# CC2564MODACMOG_1L.net
KiCad netlist of a schematic drawn in EAGLE
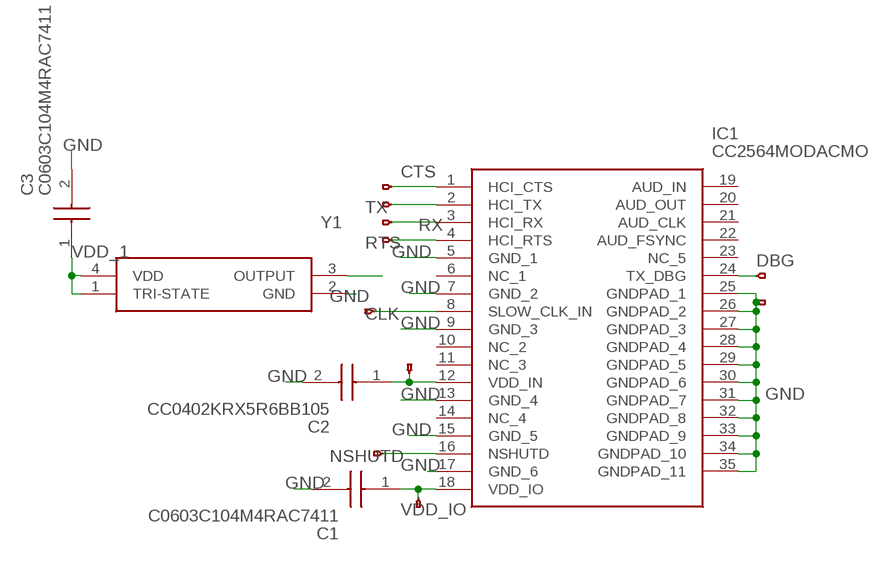
[diagram p0: schematic, sheet 1]

(export (version "E")
  (design (tool "Eeschema 10.0.6"))
  (components
    (comp (ref "C1")
      (value "C0603C104M4RAC7411")
      (footprint "eagle-import:CAPC1608X95N")
      (fields (field (name "MOUSER_PART_NUMBER") "80-C0603C104M4R7411"))
      (libsource (lib "eagle-import") (part "C0603C104M4RAC7411"))
    )
    (comp (ref "C2")
      (value "CC0402KRX5R6BB105")
      (footprint "eagle-import:CAPC1005X55N")
      (fields (field (name "MOUSER_PART_NUMBER") "603-CC402KRX5R6BB105"))
      (libsource (lib "eagle-import") (part "CC0402KRX5R6BB105"))
    )
    (comp (ref "C3")
      (value "C0603C104M4RAC7411")
      (footprint "eagle-import:CAPC1608X95N")
      (fields (field (name "MOUSER_PART_NUMBER") "80-C0603C104M4R7411"))
      (libsource (lib "eagle-import") (part "C0603C104M4RAC7411"))
    )
    (comp (ref "IC1")
      (value "CC2564MODACMOG")
      (footprint "eagle-import:MOG0035A")
      (fields (field (name "MOUSER_PART_NUMBER") "595-CC2564MODACMOG"))
      (libsource (lib "eagle-import") (part "CC2564MODACMOG"))
    )
    (comp (ref "JP1")
      (value "HEADERHOLE-HEADERHOLE")
      (footprint "eagle-import:1X1-HEADER-HOLE")
      (libsource (lib "eagle-import") (part "HEADERHOLE-HEADERHOLE"))
    )
    (comp (ref "JP2")
      (value "HEADERHOLE-HEADERHOLE")
      (footprint "eagle-import:1X1-HEADER-HOLE")
      (libsource (lib "eagle-import") (part "HEADERHOLE-HEADERHOLE"))
    )
    (comp (ref "JP7")
      (value "HEADERHOLE-HEADERHOLE")
      (footprint "eagle-import:1X1-HEADER-HOLE")
      (libsource (lib "eagle-import") (part "HEADERHOLE-HEADERHOLE"))
    )
    (comp (ref "JP8")
      (value "HEADERHOLE-HEADERHOLE")
      (footprint "eagle-import:1X1-HEADER-HOLE")
      (libsource (lib "eagle-import") (part "HEADERHOLE-HEADERHOLE"))
    )
    (comp (ref "JP9")
      (value "HEADERHOLE-HEADERHOLE")
      (footprint "eagle-import:1X1-HEADER-HOLE")
      (libsource (lib "eagle-import") (part "HEADERHOLE-HEADERHOLE"))
    )
    (comp (ref "JP10")
      (value "HEADERHOLE-HEADERHOLE")
      (footprint "eagle-import:1X1-HEADER-HOLE")
      (libsource (lib "eagle-import") (part "HEADERHOLE-HEADERHOLE"))
    )
    (comp (ref "JP11")
      (value "HEADERHOLE-HEADERHOLE")
      (footprint "eagle-import:1X1-HEADER-HOLE")
      (libsource (lib "eagle-import") (part "HEADERHOLE-HEADERHOLE"))
    )
    (comp (ref "JP12")
      (value "HEADERHOLE-HEADERHOLE")
      (footprint "eagle-import:1X1-HEADER-HOLE")
      (libsource (lib "eagle-import") (part "HEADERHOLE-HEADERHOLE"))
    )
    (comp (ref "JP13")
      (value "HEADERHOLE-HEADERHOLE")
      (footprint "eagle-import:1X1-HEADER-HOLE")
      (libsource (lib "eagle-import") (part "HEADERHOLE-HEADERHOLE"))
    )
    (comp (ref "JP14")
      (value "HEADERHOLE-HEADERHOLE")
      (footprint "eagle-import:1X1-HEADER-HOLE")
      (libsource (lib "eagle-import") (part "HEADERHOLE-HEADERHOLE"))
    )
    (comp (ref "Y1")
      (value "ECS-327MVATX-1-CN-TR")
      (footprint "eagle-import:ECS327MVATX1CNTR")
      (fields (field (name "MOUSER_PART_NUMBER") "520-327MVATX-1-CNT"))
      (libsource (lib "eagle-import") (part "ECS-327MVATX-1-CN-TR"))
    )
  )
  (nets
    (net (code "1") (name "/CLK") (class "Default")
      (node (ref "IC1") (pin "8") (pinfunction "SLOW_CLK_IN_8") (pintype "input"))
      (node (ref "JP11") (pin "1") (pinfunction "P$1_1") (pintype "bidirectional"))
    )
    (net (code "2") (name "/CTS") (class "Default")
      (node (ref "IC1") (pin "1") (pinfunction "HCI_CTS_1") (pintype "input"))
      (node (ref "JP7") (pin "1") (pinfunction "P$1_1") (pintype "bidirectional"))
    )
    (net (code "3") (name "/DBG") (class "Default")
      (node (ref "IC1") (pin "24") (pinfunction "TX_DBG_24") (pintype "output"))
      (node (ref "JP2") (pin "1") (pinfunction "P$1_1") (pintype "bidirectional"))
    )
    (net (code "4") (name "/GND") (class "Default")
      (node (ref "C1") (pin "2") (pinfunction "2_2") (pintype "bidirectional"))
      (node (ref "C2") (pin "2") (pinfunction "C2_2") (pintype "bidirectional"))
      (node (ref "C3") (pin "2") (pinfunction "2_2") (pintype "bidirectional"))
      (node (ref "IC1") (pin "13") (pinfunction "GND_4_13") (pintype "power_in"))
      (node (ref "IC1") (pin "15") (pinfunction "GND_5_15") (pintype "power_in"))
      (node (ref "IC1") (pin "17") (pinfunction "GND_6_17") (pintype "power_in"))
      (node (ref "IC1") (pin "25") (pinfunction "GNDPAD_1_25") (pintype "power_in"))
      (node (ref "IC1") (pin "26") (pinfunction "GNDPAD_2_26") (pintype "power_in"))
      (node (ref "IC1") (pin "27") (pinfunction "GNDPAD_3_27") (pintype "power_in"))
      (node (ref "IC1") (pin "28") (pinfunction "GNDPAD_4_28") (pintype "power_in"))
      (node (ref "IC1") (pin "29") (pinfunction "GNDPAD_5_29") (pintype "power_in"))
      (node (ref "IC1") (pin "30") (pinfunction "GNDPAD_6_30") (pintype "power_in"))
      (node (ref "IC1") (pin "31") (pinfunction "GNDPAD_7_31") (pintype "power_in"))
      (node (ref "IC1") (pin "32") (pinfunction "GNDPAD_8_32") (pintype "power_in"))
      (node (ref "IC1") (pin "33") (pinfunction "GNDPAD_9_33") (pintype "power_in"))
      (node (ref "IC1") (pin "34") (pinfunction "GNDPAD_10_34") (pintype "power_in"))
      (node (ref "IC1") (pin "35") (pinfunction "GNDPAD_11_35") (pintype "power_in"))
      (node (ref "IC1") (pin "5") (pinfunction "GND_1_5") (pintype "power_in"))
      (node (ref "IC1") (pin "7") (pinfunction "GND_2_7") (pintype "power_in"))
      (node (ref "IC1") (pin "9") (pinfunction "GND_3_9") (pintype "power_in"))
      (node (ref "JP1") (pin "1") (pinfunction "P$1_1") (pintype "bidirectional"))
      (node (ref "Y1") (pin "2") (pinfunction "GND_2") (pintype "bidirectional"))
    )
    (net (code "5") (name "/NSHUTD") (class "Default")
      (node (ref "IC1") (pin "16") (pinfunction "NSHUTD_16") (pintype "input"))
      (node (ref "JP14") (pin "1") (pinfunction "P$1_1") (pintype "bidirectional"))
    )
    (net (code "6") (name "/RTS") (class "Default")
      (node (ref "IC1") (pin "4") (pinfunction "HCI_RTS_4") (pintype "output"))
      (node (ref "JP10") (pin "1") (pinfunction "P$1_1") (pintype "bidirectional"))
    )
    (net (code "7") (name "/RX") (class "Default")
      (node (ref "IC1") (pin "3") (pinfunction "HCI_RX_3") (pintype "input"))
      (node (ref "JP9") (pin "1") (pinfunction "P$1_1") (pintype "bidirectional"))
    )
    (net (code "8") (name "/TX") (class "Default")
      (node (ref "IC1") (pin "2") (pinfunction "HCI_TX_2") (pintype "output"))
      (node (ref "JP8") (pin "1") (pinfunction "P$1_1") (pintype "bidirectional"))
    )
    (net (code "9") (name "/VDD_1") (class "Default")
      (node (ref "C3") (pin "1") (pinfunction "1_1") (pintype "bidirectional"))
      (node (ref "Y1") (pin "1") (pinfunction "TRI-STATE_1") (pintype "bidirectional"))
      (node (ref "Y1") (pin "4") (pinfunction "VDD_4") (pintype "bidirectional"))
    )
    (net (code "10") (name "/VDD_IO") (class "Default")
      (node (ref "C1") (pin "1") (pinfunction "1_1") (pintype "bidirectional"))
      (node (ref "IC1") (pin "18") (pinfunction "VDD_IO_18") (pintype "bidirectional"))
      (node (ref "JP13") (pin "1") (pinfunction "P$1_1") (pintype "bidirectional"))
    )
    (net (code "11") (name "Net-(C2-C1)") (class "Default")
      (node (ref "C2") (pin "1") (pinfunction "C1_1") (pintype "bidirectional"))
      (node (ref "IC1") (pin "12") (pinfunction "VDD_IN_12") (pintype "input"))
      (node (ref "JP12") (pin "1") (pinfunction "P$1_1") (pintype "bidirectional"))
    )
    (net (code "12") (name "unconnected-(IC1-AUD_CLK-Pad21)") (class "Default")
      (node (ref "IC1") (pin "21") (pinfunction "AUD_CLK_21") (pintype "bidirectional"))
    )
    (net (code "13") (name "unconnected-(IC1-AUD_FSYNC-Pad22)") (class "Default")
      (node (ref "IC1") (pin "22") (pinfunction "AUD_FSYNC_22") (pintype "bidirectional"))
    )
    (net (code "14") (name "unconnected-(IC1-AUD_IN-Pad19)") (class "Default")
      (node (ref "IC1") (pin "19") (pinfunction "AUD_IN_19") (pintype "bidirectional"))
    )
    (net (code "15") (name "unconnected-(IC1-AUD_OUT-Pad20)") (class "Default")
      (node (ref "IC1") (pin "20") (pinfunction "AUD_OUT_20") (pintype "bidirectional"))
    )
    (net (code "16") (name "unconnected-(IC1-NC_1-Pad6)") (class "Default")
      (node (ref "IC1") (pin "6") (pinfunction "NC_1_6") (pintype "bidirectional"))
    )
    (net (code "17") (name "unconnected-(IC1-NC_2-Pad10)") (class "Default")
      (node (ref "IC1") (pin "10") (pinfunction "NC_2_10") (pintype "bidirectional"))
    )
    (net (code "18") (name "unconnected-(IC1-NC_3-Pad11)") (class "Default")
      (node (ref "IC1") (pin "11") (pinfunction "NC_3_11") (pintype "bidirectional"))
    )
    (net (code "19") (name "unconnected-(IC1-NC_4-Pad14)") (class "Default")
      (node (ref "IC1") (pin "14") (pinfunction "NC_4_14") (pintype "bidirectional"))
    )
    (net (code "20") (name "unconnected-(IC1-NC_5-Pad23)") (class "Default")
      (node (ref "IC1") (pin "23") (pinfunction "NC_5_23") (pintype "bidirectional"))
    )
    (net (code "21") (name "unconnected-(Y1-OUTPUT-Pad3)") (class "Default")
      (node (ref "Y1") (pin "3") (pinfunction "OUTPUT_3") (pintype "bidirectional"))
    )
  )
)
